# schematic_final.net
KiCad netlist of a schematic drawn in EAGLE
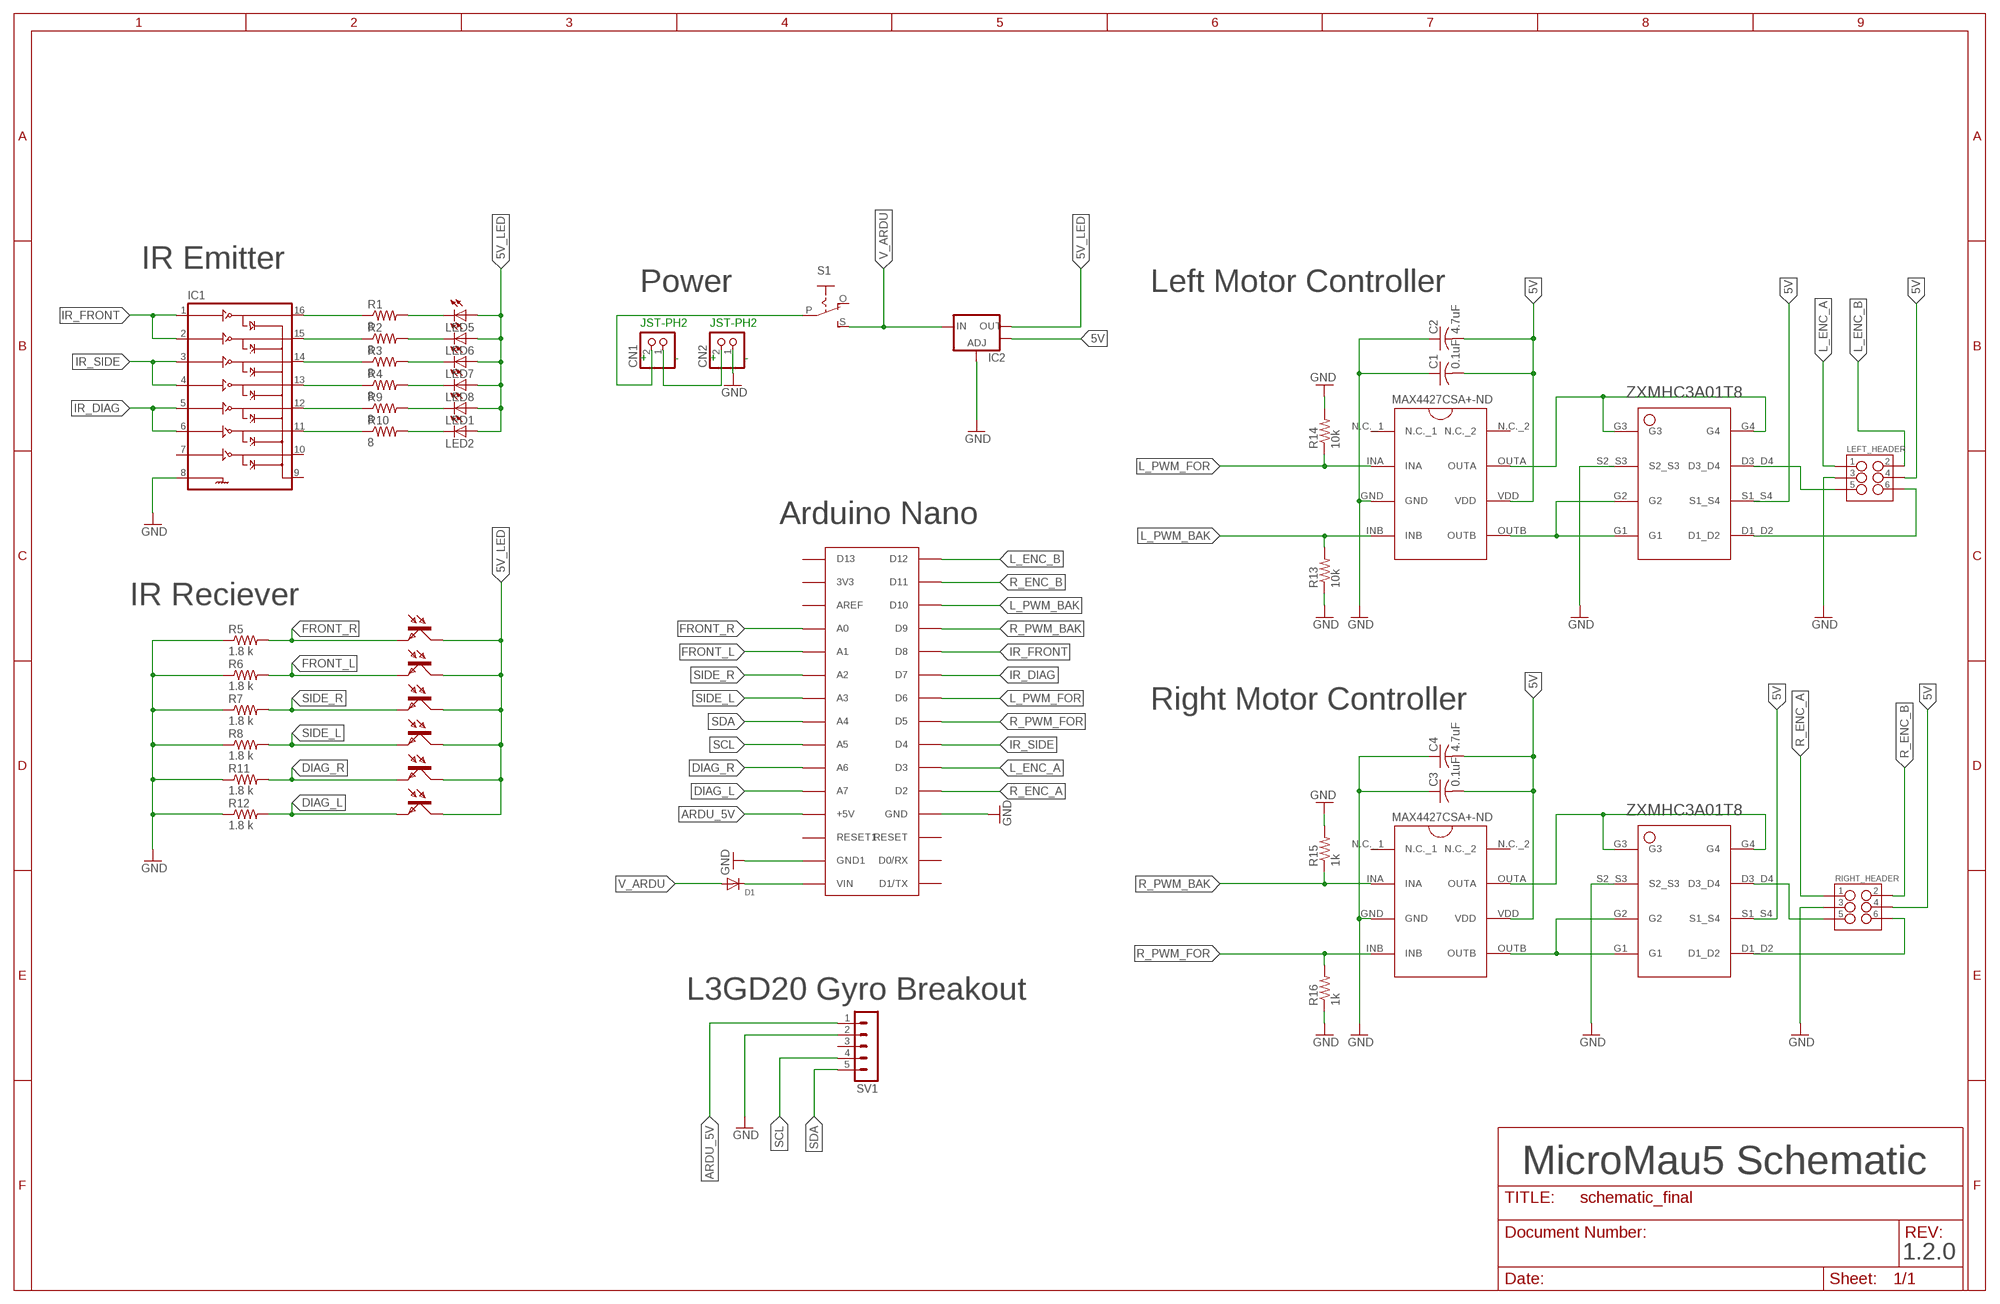
[diagram p0: schematic, sheet 1]

(export (version "E")
  (design (tool "Eeschema 10.0.6"))
  (components
    (comp (ref "C1")
      (value "0.1uF")
      (footprint "eagle-import:C0805")
      (libsource (lib "eagle-import") (part "C-USC0805"))
    )
    (comp (ref "C2")
      (value "4.7uF")
      (footprint "eagle-import:C0805")
      (libsource (lib "eagle-import") (part "C-USC0805"))
    )
    (comp (ref "C3")
      (value "0.1uF")
      (footprint "eagle-import:C0805")
      (libsource (lib "eagle-import") (part "C-USC0805"))
    )
    (comp (ref "C4")
      (value "4.7uF")
      (footprint "eagle-import:C0805")
      (libsource (lib "eagle-import") (part "C-USC0805"))
    )
    (comp (ref "CN1")
      (value "JST_2PIN-THM")
      (footprint "eagle-import:JST-PH-2-THM")
      (libsource (lib "eagle-import") (part "JST_2PIN-THM"))
    )
    (comp (ref "CN2")
      (value "JST_2PIN-THM")
      (footprint "eagle-import:JST-PH-2-THM")
      (libsource (lib "eagle-import") (part "JST_2PIN-THM"))
    )
    (comp (ref "D1")
      (value "DIODESOD-123")
      (footprint "eagle-import:SOD-123")
      (libsource (lib "eagle-import") (part "DIODESOD-123"))
    )
    (comp (ref "IC1")
      (value "IC_ULN2003-TSSOP-16")
      (footprint "eagle-import:TSSOP-16")
      (libsource (lib "eagle-import") (part "IC_ULN2003-TSSOP-16"))
    )
    (comp (ref "IC2")
      (value "V_REG_LM1117SOT223")
      (footprint "eagle-import:SOT223")
      (libsource (lib "eagle-import") (part "V_REG_LM1117SOT223"))
    )
    (comp (ref "LED1")
      (value "LED5MM")
      (footprint "eagle-import:LED5MM")
      (libsource (lib "eagle-import") (part "LED5MM"))
    )
    (comp (ref "LED2")
      (value "LED5MM")
      (footprint "eagle-import:LED5MM")
      (libsource (lib "eagle-import") (part "LED5MM"))
    )
    (comp (ref "LED5")
      (value "LED5MM")
      (footprint "eagle-import:LED5MM")
      (libsource (lib "eagle-import") (part "LED5MM"))
    )
    (comp (ref "LED6")
      (value "LED5MM")
      (footprint "eagle-import:LED5MM")
      (libsource (lib "eagle-import") (part "LED5MM"))
    )
    (comp (ref "LED7")
      (value "LED5MM")
      (footprint "eagle-import:LED5MM")
      (libsource (lib "eagle-import") (part "LED5MM"))
    )
    (comp (ref "LED8")
      (value "LED5MM")
      (footprint "eagle-import:LED5MM")
      (libsource (lib "eagle-import") (part "LED5MM"))
    )
    (comp (ref "LEFT_HEADER")
      (value "M03X2SHROUD")
      (footprint "eagle-import:2X3-SHROUDED")
      (libsource (lib "eagle-import") (part "M03X2SHROUD"))
    )
    (comp (ref "R1")
      (value "8")
      (footprint "eagle-import:M0805")
      (libsource (lib "eagle-import") (part "R-US_M0805"))
    )
    (comp (ref "R2")
      (value "8")
      (footprint "eagle-import:M0805")
      (libsource (lib "eagle-import") (part "R-US_M0805"))
    )
    (comp (ref "R3")
      (value "8")
      (footprint "eagle-import:M0805")
      (libsource (lib "eagle-import") (part "R-US_M0805"))
    )
    (comp (ref "R4")
      (value "8")
      (footprint "eagle-import:M0805")
      (libsource (lib "eagle-import") (part "R-US_M0805"))
    )
    (comp (ref "R5")
      (value "1.8 k")
      (footprint "eagle-import:R0805")
      (libsource (lib "eagle-import") (part "R-US_R0805"))
    )
    (comp (ref "R6")
      (value "1.8 k")
      (footprint "eagle-import:R0805")
      (libsource (lib "eagle-import") (part "R-US_R0805"))
    )
    (comp (ref "R7")
      (value "1.8 k")
      (footprint "eagle-import:R0805")
      (libsource (lib "eagle-import") (part "R-US_R0805"))
    )
    (comp (ref "R8")
      (value "1.8 k")
      (footprint "eagle-import:R0805")
      (libsource (lib "eagle-import") (part "R-US_R0805"))
    )
    (comp (ref "R9")
      (value "8")
      (footprint "eagle-import:M0805")
      (libsource (lib "eagle-import") (part "R-US_M0805"))
    )
    (comp (ref "R10")
      (value "8")
      (footprint "eagle-import:M0805")
      (libsource (lib "eagle-import") (part "R-US_M0805"))
    )
    (comp (ref "R11")
      (value "1.8 k")
      (footprint "eagle-import:R0805")
      (libsource (lib "eagle-import") (part "R-US_R0805"))
    )
    (comp (ref "R12")
      (value "1.8 k")
      (footprint "eagle-import:R0805")
      (libsource (lib "eagle-import") (part "R-US_R0805"))
    )
    (comp (ref "R13")
      (value "10k")
      (footprint "eagle-import:R0805")
      (libsource (lib "eagle-import") (part "R-US_R0805"))
    )
    (comp (ref "R14")
      (value "10k")
      (footprint "eagle-import:R0805")
      (libsource (lib "eagle-import") (part "R-US_R0805"))
    )
    (comp (ref "R15")
      (value "1k")
      (footprint "eagle-import:R0805")
      (libsource (lib "eagle-import") (part "R-US_R0805"))
    )
    (comp (ref "R16")
      (value "1k")
      (footprint "eagle-import:R0805")
      (libsource (lib "eagle-import") (part "R-US_R0805"))
    )
    (comp (ref "RIGHT_HEADER")
      (value "M03X2SHROUD")
      (footprint "eagle-import:2X3-SHROUDED")
      (libsource (lib "eagle-import") (part "M03X2SHROUD"))
    )
    (comp (ref "S1")
      (value "EG1218S")
      (footprint "eagle-import:EG1218")
      (libsource (lib "eagle-import") (part "EG1218S"))
    )
    (comp (ref "SV1")
      (value "MA05-1")
      (footprint "eagle-import:MA05-1")
      (libsource (lib "eagle-import") (part "MA05-1"))
    )
    (comp (ref "T1")
      (value "BPX81")
      (footprint "eagle-import:BPX81")
      (libsource (lib "eagle-import") (part "BPX81"))
    )
    (comp (ref "T2")
      (value "BPX81")
      (footprint "eagle-import:BPX81")
      (libsource (lib "eagle-import") (part "BPX81"))
    )
    (comp (ref "T3")
      (value "BPX81")
      (footprint "eagle-import:BPX81")
      (libsource (lib "eagle-import") (part "BPX81"))
    )
    (comp (ref "T4")
      (value "BPX81")
      (footprint "eagle-import:BPX81")
      (libsource (lib "eagle-import") (part "BPX81"))
    )
    (comp (ref "T5")
      (value "BPX81")
      (footprint "eagle-import:BPX81")
      (libsource (lib "eagle-import") (part "BPX81"))
    )
    (comp (ref "T6")
      (value "BPX81")
      (footprint "eagle-import:BPX81")
      (libsource (lib "eagle-import") (part "BPX81"))
    )
    (comp (ref "U$1")
      (value "MAX4427CSA+-ND")
      (footprint "eagle-import:MAX4427CSA+-ND")
      (libsource (lib "eagle-import") (part "MAX4427CSA+-ND"))
    )
    (comp (ref "U$2")
      (value "ZXMHC3A01T8")
      (footprint "eagle-import:ZXMHC3A01T8")
      (libsource (lib "eagle-import") (part "ZXMHC3A01T8"))
    )
    (comp (ref "U$3")
      (value "ARDUINONANO")
      (footprint "eagle-import:PDIP-32")
      (libsource (lib "eagle-import") (part "ARDUINONANO"))
    )
    (comp (ref "U$4")
      (value "MAX4427CSA+-ND")
      (footprint "eagle-import:MAX4427CSA+-ND")
      (libsource (lib "eagle-import") (part "MAX4427CSA+-ND"))
    )
    (comp (ref "U$5")
      (value "ZXMHC3A01T8")
      (footprint "eagle-import:ZXMHC3A01T8")
      (libsource (lib "eagle-import") (part "ZXMHC3A01T8"))
    )
  )
  (nets
    (net (code "1") (name "5V") (class "Default")
      (node (ref "C1") (pin "2") (pinfunction "2_2") (pintype "passive"))
      (node (ref "C2") (pin "2") (pinfunction "2_2") (pintype "passive"))
      (node (ref "C3") (pin "2") (pinfunction "2_2") (pintype "passive"))
      (node (ref "C4") (pin "2") (pinfunction "2_2") (pintype "passive"))
      (node (ref "IC2") (pin "4") (pinfunction "OUT_4") (pintype "output"))
      (node (ref "LEFT_HEADER") (pin "4") (pinfunction "4_4") (pintype "bidirectional"))
      (node (ref "RIGHT_HEADER") (pin "4") (pinfunction "4_4") (pintype "bidirectional"))
      (node (ref "U$1") (pin "VDD") (pinfunction "VDD_VDD") (pintype "bidirectional"))
      (node (ref "U$2") (pin "S1_S4") (pinfunction "S1_S4_S1_S4") (pintype "bidirectional"))
      (node (ref "U$4") (pin "VDD") (pinfunction "VDD_VDD") (pintype "bidirectional"))
      (node (ref "U$5") (pin "S1_S4") (pinfunction "S1_S4_S1_S4") (pintype "bidirectional"))
    )
    (net (code "2") (name "5V_LED") (class "Default")
      (node (ref "IC2") (pin "2") (pinfunction "OUT_2") (pintype "output"))
      (node (ref "LED1") (pin "A") (pinfunction "A_A") (pintype "passive"))
      (node (ref "LED2") (pin "A") (pinfunction "A_A") (pintype "passive"))
      (node (ref "LED5") (pin "A") (pinfunction "A_A") (pintype "passive"))
      (node (ref "LED6") (pin "A") (pinfunction "A_A") (pintype "passive"))
      (node (ref "LED7") (pin "A") (pinfunction "A_A") (pintype "passive"))
      (node (ref "LED8") (pin "A") (pinfunction "A_A") (pintype "passive"))
      (node (ref "T1") (pin "C") (pinfunction "C_C") (pintype "passive"))
      (node (ref "T2") (pin "C") (pinfunction "C_C") (pintype "passive"))
      (node (ref "T3") (pin "C") (pinfunction "C_C") (pintype "passive"))
      (node (ref "T4") (pin "C") (pinfunction "C_C") (pintype "passive"))
      (node (ref "T5") (pin "C") (pinfunction "C_C") (pintype "passive"))
      (node (ref "T6") (pin "C") (pinfunction "C_C") (pintype "passive"))
    )
    (net (code "3") (name "ARDU_5V") (class "Default")
      (node (ref "SV1") (pin "1") (pinfunction "1_1") (pintype "passive"))
      (node (ref "U$3") (pin "+5V") (pinfunction "+5V_+5V") (pintype "bidirectional"))
    )
    (net (code "4") (name "DIAG_L") (class "Default")
      (node (ref "R12") (pin "2") (pinfunction "2_2") (pintype "passive"))
      (node (ref "T6") (pin "E") (pinfunction "E_E") (pintype "passive"))
      (node (ref "U$3") (pin "A7") (pinfunction "A7_A7") (pintype "bidirectional"))
    )
    (net (code "5") (name "DIAG_R") (class "Default")
      (node (ref "R11") (pin "2") (pinfunction "2_2") (pintype "passive"))
      (node (ref "T5") (pin "E") (pinfunction "E_E") (pintype "passive"))
      (node (ref "U$3") (pin "A6") (pinfunction "A6_A6") (pintype "bidirectional"))
    )
    (net (code "6") (name "FRONT_L") (class "Default")
      (node (ref "R6") (pin "2") (pinfunction "2_2") (pintype "passive"))
      (node (ref "T3") (pin "E") (pinfunction "E_E") (pintype "passive"))
      (node (ref "U$3") (pin "A1") (pinfunction "A1_A1") (pintype "bidirectional"))
    )
    (net (code "7") (name "FRONT_R") (class "Default")
      (node (ref "R5") (pin "2") (pinfunction "2_2") (pintype "passive"))
      (node (ref "T2") (pin "E") (pinfunction "E_E") (pintype "passive"))
      (node (ref "U$3") (pin "A0") (pinfunction "A0_A0") (pintype "bidirectional"))
    )
    (net (code "8") (name "GND") (class "Default")
      (node (ref "C1") (pin "1") (pinfunction "1_1") (pintype "passive"))
      (node (ref "C2") (pin "1") (pinfunction "1_1") (pintype "passive"))
      (node (ref "C3") (pin "1") (pinfunction "1_1") (pintype "passive"))
      (node (ref "C4") (pin "1") (pinfunction "1_1") (pintype "passive"))
      (node (ref "CN2") (pin "1") (pinfunction "2_1") (pintype "passive"))
      (node (ref "IC1") (pin "8") (pinfunction "GND_8") (pintype "bidirectional"))
      (node (ref "IC2") (pin "1") (pinfunction "ADJ_1") (pintype "input"))
      (node (ref "LEFT_HEADER") (pin "3") (pinfunction "3_3") (pintype "bidirectional"))
      (node (ref "R11") (pin "1") (pinfunction "1_1") (pintype "passive"))
      (node (ref "R12") (pin "1") (pinfunction "1_1") (pintype "passive"))
      (node (ref "R13") (pin "1") (pinfunction "1_1") (pintype "passive"))
      (node (ref "R14") (pin "2") (pinfunction "2_2") (pintype "passive"))
      (node (ref "R15") (pin "2") (pinfunction "2_2") (pintype "passive"))
      (node (ref "R16") (pin "1") (pinfunction "1_1") (pintype "passive"))
      (node (ref "R5") (pin "1") (pinfunction "1_1") (pintype "passive"))
      (node (ref "R6") (pin "1") (pinfunction "1_1") (pintype "passive"))
      (node (ref "R7") (pin "1") (pinfunction "1_1") (pintype "passive"))
      (node (ref "R8") (pin "1") (pinfunction "1_1") (pintype "passive"))
      (node (ref "RIGHT_HEADER") (pin "3") (pinfunction "3_3") (pintype "bidirectional"))
      (node (ref "SV1") (pin "2") (pinfunction "2_2") (pintype "passive"))
      (node (ref "U$1") (pin "GND") (pinfunction "GND_GND") (pintype "bidirectional"))
      (node (ref "U$2") (pin "S2_S3") (pinfunction "S2_S3_S2_S3") (pintype "bidirectional"))
      (node (ref "U$3") (pin "GND") (pinfunction "GND_GND") (pintype "bidirectional"))
      (node (ref "U$3") (pin "GND1") (pinfunction "GND1_GND1") (pintype "bidirectional"))
      (node (ref "U$4") (pin "GND") (pinfunction "GND_GND") (pintype "bidirectional"))
      (node (ref "U$5") (pin "S2_S3") (pinfunction "S2_S3_S2_S3") (pintype "bidirectional"))
    )
    (net (code "9") (name "IR_DIAG") (class "Default")
      (node (ref "IC1") (pin "5") (pinfunction "5B_5") (pintype "bidirectional"))
      (node (ref "IC1") (pin "6") (pinfunction "6B_6") (pintype "bidirectional"))
      (node (ref "U$3") (pin "D7") (pinfunction "D7_D7") (pintype "bidirectional"))
    )
    (net (code "10") (name "IR_FRONT") (class "Default")
      (node (ref "IC1") (pin "1") (pinfunction "1B_1") (pintype "bidirectional"))
      (node (ref "IC1") (pin "2") (pinfunction "2B_2") (pintype "bidirectional"))
      (node (ref "U$3") (pin "D8") (pinfunction "D8_D8") (pintype "bidirectional"))
    )
    (net (code "11") (name "IR_SIDE") (class "Default")
      (node (ref "IC1") (pin "3") (pinfunction "3B_3") (pintype "bidirectional"))
      (node (ref "IC1") (pin "4") (pinfunction "4B_4") (pintype "bidirectional"))
      (node (ref "U$3") (pin "D4") (pinfunction "D4_D4") (pintype "bidirectional"))
    )
    (net (code "12") (name "L_ENC_A") (class "Default")
      (node (ref "LEFT_HEADER") (pin "1") (pinfunction "1_1") (pintype "bidirectional"))
      (node (ref "U$3") (pin "D3") (pinfunction "D3_D3") (pintype "bidirectional"))
    )
    (net (code "13") (name "L_ENC_B") (class "Default")
      (node (ref "LEFT_HEADER") (pin "2") (pinfunction "2_2") (pintype "bidirectional"))
      (node (ref "U$3") (pin "D12") (pinfunction "D12_D12") (pintype "bidirectional"))
    )
    (net (code "14") (name "L_PWM_BAK") (class "Default")
      (node (ref "R13") (pin "2") (pinfunction "2_2") (pintype "passive"))
      (node (ref "U$1") (pin "INB") (pinfunction "INB_INB") (pintype "bidirectional"))
      (node (ref "U$3") (pin "D10") (pinfunction "D10_D10") (pintype "bidirectional"))
    )
    (net (code "15") (name "L_PWM_FOR") (class "Default")
      (node (ref "R14") (pin "1") (pinfunction "1_1") (pintype "passive"))
      (node (ref "U$1") (pin "INA") (pinfunction "INA_INA") (pintype "bidirectional"))
      (node (ref "U$3") (pin "D6") (pinfunction "D6_D6") (pintype "bidirectional"))
    )
    (net (code "16") (name "Net-(CN1-1)") (class "Default")
      (node (ref "CN1") (pin "2") (pinfunction "1_2") (pintype "passive"))
      (node (ref "S1") (pin "P") (pinfunction "P_P") (pintype "passive"))
    )
    (net (code "17") (name "Net-(CN1-2)") (class "Default")
      (node (ref "CN1") (pin "1") (pinfunction "2_1") (pintype "passive"))
      (node (ref "CN2") (pin "2") (pinfunction "1_2") (pintype "passive"))
    )
    (net (code "18") (name "Net-(D1-PadC)") (class "Default")
      (node (ref "D1") (pin "C") (pinfunction "C_C") (pintype "passive"))
      (node (ref "U$3") (pin "VIN") (pinfunction "VIN_VIN") (pintype "bidirectional"))
    )
    (net (code "19") (name "Net-(IC1-1C)") (class "Default")
      (node (ref "IC1") (pin "16") (pinfunction "1C_16") (pintype "bidirectional"))
      (node (ref "R1") (pin "1") (pinfunction "1_1") (pintype "passive"))
    )
    (net (code "20") (name "Net-(IC1-2C)") (class "Default")
      (node (ref "IC1") (pin "15") (pinfunction "2C_15") (pintype "bidirectional"))
      (node (ref "R2") (pin "1") (pinfunction "1_1") (pintype "passive"))
    )
    (net (code "21") (name "Net-(IC1-3C)") (class "Default")
      (node (ref "IC1") (pin "14") (pinfunction "3C_14") (pintype "bidirectional"))
      (node (ref "R3") (pin "1") (pinfunction "1_1") (pintype "passive"))
    )
    (net (code "22") (name "Net-(IC1-4C)") (class "Default")
      (node (ref "IC1") (pin "13") (pinfunction "4C_13") (pintype "bidirectional"))
      (node (ref "R4") (pin "1") (pinfunction "1_1") (pintype "passive"))
    )
    (net (code "23") (name "Net-(IC1-5C)") (class "Default")
      (node (ref "IC1") (pin "12") (pinfunction "5C_12") (pintype "bidirectional"))
      (node (ref "R9") (pin "1") (pinfunction "1_1") (pintype "passive"))
    )
    (net (code "24") (name "Net-(IC1-6C)") (class "Default")
      (node (ref "IC1") (pin "11") (pinfunction "6C_11") (pintype "bidirectional"))
      (node (ref "R10") (pin "1") (pinfunction "1_1") (pintype "passive"))
    )
    (net (code "25") (name "Net-(LED1-C)") (class "Default")
      (node (ref "LED1") (pin "K") (pinfunction "C_K") (pintype "passive"))
      (node (ref "R9") (pin "2") (pinfunction "2_2") (pintype "passive"))
    )
    (net (code "26") (name "Net-(LED2-C)") (class "Default")
      (node (ref "LED2") (pin "K") (pinfunction "C_K") (pintype "passive"))
      (node (ref "R10") (pin "2") (pinfunction "2_2") (pintype "passive"))
    )
    (net (code "27") (name "Net-(LED5-C)") (class "Default")
      (node (ref "LED5") (pin "K") (pinfunction "C_K") (pintype "passive"))
      (node (ref "R1") (pin "2") (pinfunction "2_2") (pintype "passive"))
    )
    (net (code "28") (name "Net-(LED6-C)") (class "Default")
      (node (ref "LED6") (pin "K") (pinfunction "C_K") (pintype "passive"))
      (node (ref "R2") (pin "2") (pinfunction "2_2") (pintype "passive"))
    )
    (net (code "29") (name "Net-(LED7-C)") (class "Default")
      (node (ref "LED7") (pin "K") (pinfunction "C_K") (pintype "passive"))
      (node (ref "R3") (pin "2") (pinfunction "2_2") (pintype "passive"))
    )
    (net (code "30") (name "Net-(LED8-C)") (class "Default")
      (node (ref "LED8") (pin "K") (pinfunction "C_K") (pintype "passive"))
      (node (ref "R4") (pin "2") (pinfunction "2_2") (pintype "passive"))
    )
    (net (code "31") (name "Net-(LEFT_HEADER-Pad5)") (class "Default")
      (node (ref "LEFT_HEADER") (pin "5") (pinfunction "5_5") (pintype "bidirectional"))
      (node (ref "U$2") (pin "D3_D4") (pinfunction "D3_D4_D3_D4") (pintype "bidirectional"))
    )
    (net (code "32") (name "Net-(LEFT_HEADER-Pad6)") (class "Default")
      (node (ref "LEFT_HEADER") (pin "6") (pinfunction "6_6") (pintype "bidirectional"))
      (node (ref "U$2") (pin "D1_D2") (pinfunction "D1_D2_D1_D2") (pintype "bidirectional"))
    )
    (net (code "33") (name "Net-(RIGHT_HEADER-Pad5)") (class "Default")
      (node (ref "RIGHT_HEADER") (pin "5") (pinfunction "5_5") (pintype "bidirectional"))
      (node (ref "U$5") (pin "D3_D4") (pinfunction "D3_D4_D3_D4") (pintype "bidirectional"))
    )
    (net (code "34") (name "Net-(RIGHT_HEADER-Pad6)") (class "Default")
      (node (ref "RIGHT_HEADER") (pin "6") (pinfunction "6_6") (pintype "bidirectional"))
      (node (ref "U$5") (pin "D1_D2") (pinfunction "D1_D2_D1_D2") (pintype "bidirectional"))
    )
    (net (code "35") (name "Net-(U$1-PadOUTA)") (class "Default")
      (node (ref "U$1") (pin "OUTA") (pinfunction "OUTA_OUTA") (pintype "bidirectional"))
      (node (ref "U$2") (pin "G3") (pinfunction "G3_G3") (pintype "bidirectional"))
      (node (ref "U$2") (pin "G4") (pinfunction "G4_G4") (pintype "bidirectional"))
    )
    (net (code "36") (name "Net-(U$1-PadOUTB)") (class "Default")
      (node (ref "U$1") (pin "OUTB") (pinfunction "OUTB_OUTB") (pintype "bidirectional"))
      (node (ref "U$2") (pin "G1") (pinfunction "G1_G1") (pintype "bidirectional"))
      (node (ref "U$2") (pin "G2") (pinfunction "G2_G2") (pintype "bidirectional"))
    )
    (net (code "37") (name "Net-(U$4-PadOUTA)") (class "Default")
      (node (ref "U$4") (pin "OUTA") (pinfunction "OUTA_OUTA") (pintype "bidirectional"))
      (node (ref "U$5") (pin "G3") (pinfunction "G3_G3") (pintype "bidirectional"))
      (node (ref "U$5") (pin "G4") (pinfunction "G4_G4") (pintype "bidirectional"))
    )
    (net (code "38") (name "Net-(U$4-PadOUTB)") (class "Default")
      (node (ref "U$4") (pin "OUTB") (pinfunction "OUTB_OUTB") (pintype "bidirectional"))
      (node (ref "U$5") (pin "G1") (pinfunction "G1_G1") (pintype "bidirectional"))
      (node (ref "U$5") (pin "G2") (pinfunction "G2_G2") (pintype "bidirectional"))
    )
    (net (code "39") (name "R_ENC_A") (class "Default")
      (node (ref "RIGHT_HEADER") (pin "1") (pinfunction "1_1") (pintype "bidirectional"))
      (node (ref "U$3") (pin "D2") (pinfunction "D2_D2") (pintype "bidirectional"))
    )
    (net (code "40") (name "R_ENC_B") (class "Default")
      (node (ref "RIGHT_HEADER") (pin "2") (pinfunction "2_2") (pintype "bidirectional"))
      (node (ref "U$3") (pin "D11") (pinfunction "D11_D11") (pintype "bidirectional"))
    )
    (net (code "41") (name "R_PWM_BAK") (class "Default")
      (node (ref "R15") (pin "1") (pinfunction "1_1") (pintype "passive"))
      (node (ref "U$3") (pin "D9") (pinfunction "D9_D9") (pintype "bidirectional"))
      (node (ref "U$4") (pin "INA") (pinfunction "INA_INA") (pintype "bidirectional"))
    )
    (net (code "42") (name "R_PWM_FOR") (class "Default")
      (node (ref "R16") (pin "2") (pinfunction "2_2") (pintype "passive"))
      (node (ref "U$3") (pin "D5") (pinfunction "D5_D5") (pintype "bidirectional"))
      (node (ref "U$4") (pin "INB") (pinfunction "INB_INB") (pintype "bidirectional"))
    )
    (net (code "43") (name "SCL") (class "Default")
      (node (ref "SV1") (pin "4") (pinfunction "4_4") (pintype "passive"))
      (node (ref "U$3") (pin "A5") (pinfunction "A5_A5") (pintype "bidirectional"))
    )
    (net (code "44") (name "SDA") (class "Default")
      (node (ref "SV1") (pin "5") (pinfunction "5_5") (pintype "passive"))
      (node (ref "U$3") (pin "A4") (pinfunction "A4_A4") (pintype "bidirectional"))
    )
    (net (code "45") (name "SIDE_L") (class "Default")
      (node (ref "R8") (pin "2") (pinfunction "2_2") (pintype "passive"))
      (node (ref "T4") (pin "E") (pinfunction "E_E") (pintype "passive"))
      (node (ref "U$3") (pin "A3") (pinfunction "A3_A3") (pintype "bidirectional"))
    )
    (net (code "46") (name "SIDE_R") (class "Default")
      (node (ref "R7") (pin "2") (pinfunction "2_2") (pintype "passive"))
      (node (ref "T1") (pin "E") (pinfunction "E_E") (pintype "passive"))
      (node (ref "U$3") (pin "A2") (pinfunction "A2_A2") (pintype "bidirectional"))
    )
    (net (code "47") (name "V_ARDU") (class "Default")
      (node (ref "D1") (pin "A") (pinfunction "A_A") (pintype "passive"))
      (node (ref "IC2") (pin "3") (pinfunction "IN_3") (pintype "input"))
      (node (ref "S1") (pin "S") (pinfunction "S_S") (pintype "passive"))
    )
    (net (code "48") (name "unconnected-(IC1-7B-Pad7)") (class "Default")
      (node (ref "IC1") (pin "7") (pinfunction "7B_7") (pintype "bidirectional"))
    )
    (net (code "49") (name "unconnected-(IC1-7C-Pad10)") (class "Default")
      (node (ref "IC1") (pin "10") (pinfunction "7C_10") (pintype "bidirectional"))
    )
    (net (code "50") (name "unconnected-(IC1-COM-Pad9)") (class "Default")
      (node (ref "IC1") (pin "9") (pinfunction "COM_9") (pintype "bidirectional"))
    )
    (net (code "51") (name "unconnected-(S1-PadO)") (class "Default")
      (node (ref "S1") (pin "O") (pinfunction "O_O") (pintype "passive"))
    )
    (net (code "52") (name "unconnected-(SV1-Pad3)") (class "Default")
      (node (ref "SV1") (pin "3") (pinfunction "3_3") (pintype "passive"))
    )
    (net (code "53") (name "unconnected-(U$1-PadN.C._1)") (class "Default")
      (node (ref "U$1") (pin "N.C._1") (pinfunction "N.C._1_N.C._1") (pintype "bidirectional"))
    )
    (net (code "54") (name "unconnected-(U$1-PadN.C._2)") (class "Default")
      (node (ref "U$1") (pin "N.C._2") (pinfunction "N.C._2_N.C._2") (pintype "bidirectional"))
    )
    (net (code "55") (name "unconnected-(U$3-Pad3V3)") (class "Default")
      (node (ref "U$3") (pin "3V3") (pinfunction "3V3_3V3") (pintype "bidirectional"))
    )
    (net (code "56") (name "unconnected-(U$3-PadAREF)") (class "Default")
      (node (ref "U$3") (pin "AREF") (pinfunction "AREF_AREF") (pintype "bidirectional"))
    )
    (net (code "57") (name "unconnected-(U$3-PadD0{slash}RX)") (class "Default")
      (node (ref "U$3") (pin "D0/RX") (pinfunction "D0/RX_D0/RX") (pintype "bidirectional"))
    )
    (net (code "58") (name "unconnected-(U$3-PadD1{slash}TX)") (class "Default")
      (node (ref "U$3") (pin "D1/TX") (pinfunction "D1/TX_D1/TX") (pintype "bidirectional"))
    )
    (net (code "59") (name "unconnected-(U$3-PadD13)") (class "Default")
      (node (ref "U$3") (pin "D13") (pinfunction "D13_D13") (pintype "bidirectional"))
    )
    (net (code "60") (name "unconnected-(U$3-PadRESET)") (class "Default")
      (node (ref "U$3") (pin "RESET") (pinfunction "RESET_RESET") (pintype "bidirectional"))
    )
    (net (code "61") (name "unconnected-(U$3-PadRESET1)") (class "Default")
      (node (ref "U$3") (pin "RESET1") (pinfunction "RESET1_RESET1") (pintype "bidirectional"))
    )
    (net (code "62") (name "unconnected-(U$4-PadN.C._1)") (class "Default")
      (node (ref "U$4") (pin "N.C._1") (pinfunction "N.C._1_N.C._1") (pintype "bidirectional"))
    )
    (net (code "63") (name "unconnected-(U$4-PadN.C._2)") (class "Default")
      (node (ref "U$4") (pin "N.C._2") (pinfunction "N.C._2_N.C._2") (pintype "bidirectional"))
    )
  )
)
